# SCH_PCB_Dashboy_subboard_2023-03-29.net
KiCad netlist of a schematic drawn in EasyEDA
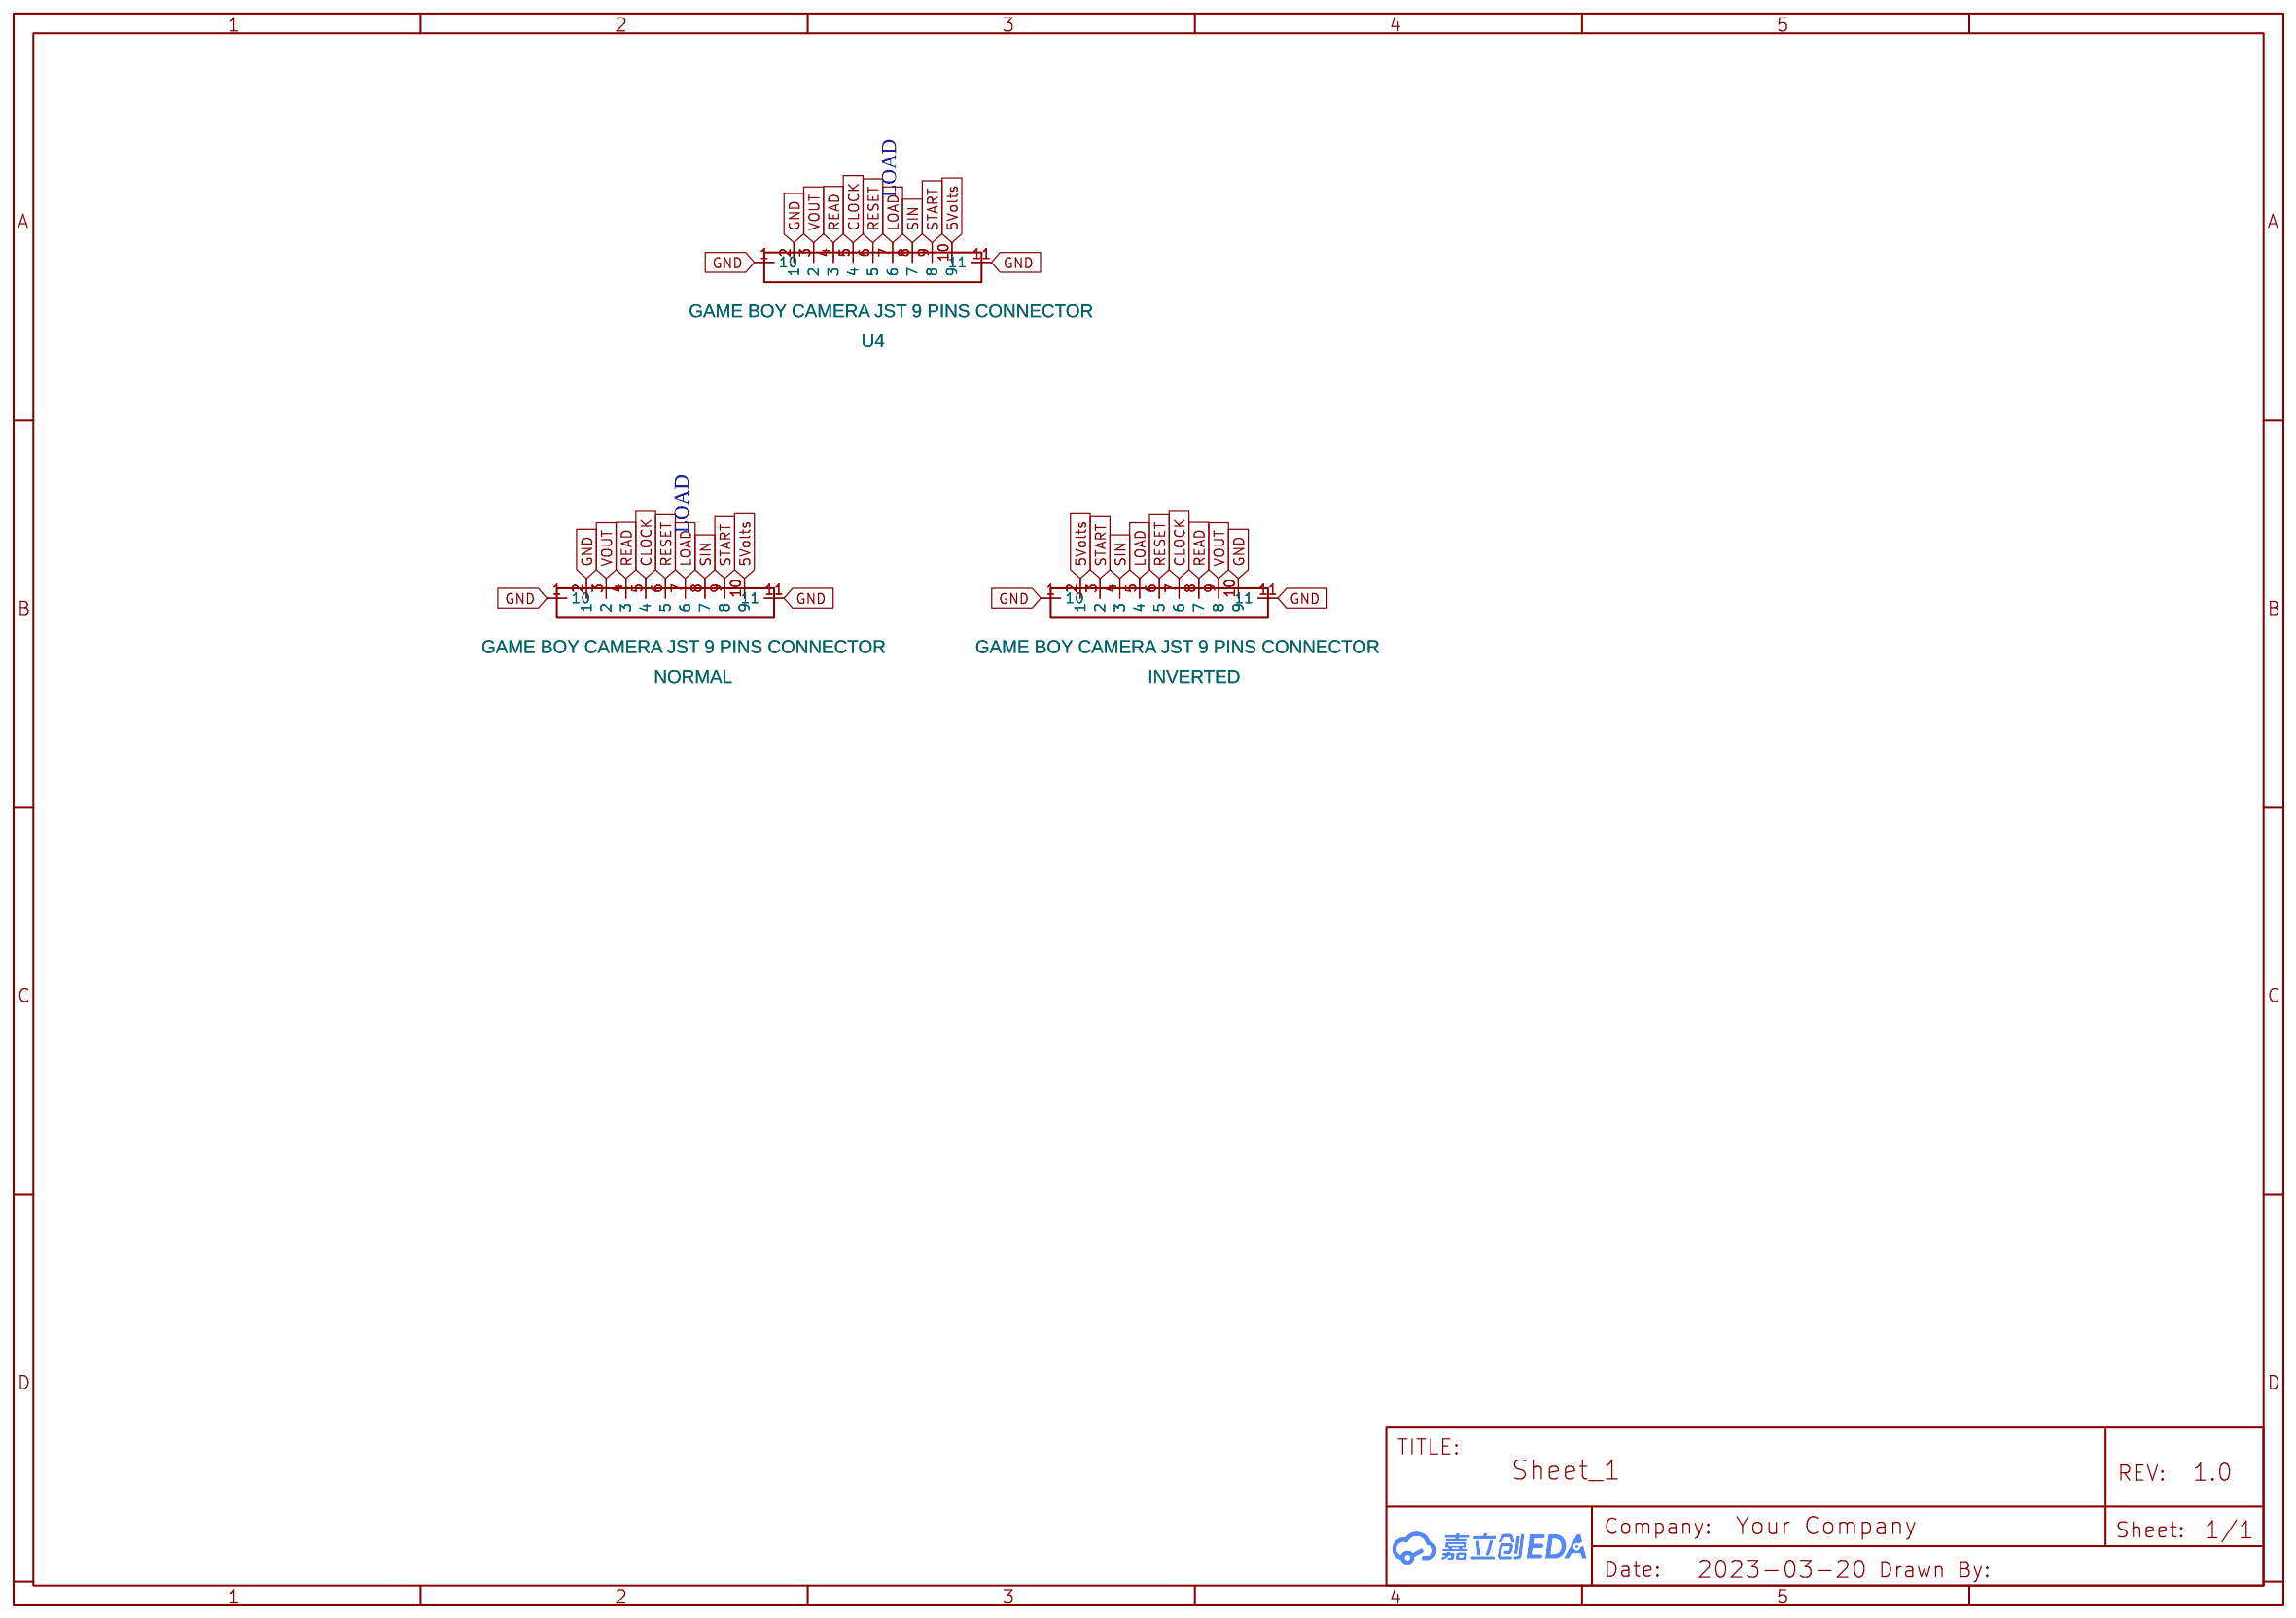
[diagram p0: schematic sheet]

(export (version "E")
  (design (tool "Eeschema 10.0.6"))
  (components
    (comp (ref "INVERTED")
      (value "GAME BOY CAMERA JST 9 PINS CONNECTOR")
      (libsource (lib "") (part "GAME BOY CAMERA JST 9 PINS CONNECTOR_2"))
    )
    (comp (ref "NORMAL")
      (value "GAME BOY CAMERA JST 9 PINS CONNECTOR")
      (libsource (lib "") (part "GAME BOY CAMERA JST 9 PINS CONNECTOR_1"))
    )
    (comp (ref "U4")
      (value "GAME BOY CAMERA JST 9 PINS CONNECTOR")
      (libsource (lib "") (part "GAME BOY CAMERA JST 9 PINS CONNECTOR"))
    )
  )
  (nets
    (net (code "1") (name "5Volts") (class "Default")
      (node (ref "INVERTED") (pin "2") (pinfunction "1_2") (pintype "unspecified"))
      (node (ref "NORMAL") (pin "10") (pinfunction "9_10") (pintype "unspecified"))
      (node (ref "U4") (pin "10") (pinfunction "9_10") (pintype "unspecified"))
    )
    (net (code "2") (name "CLOCK") (class "Default")
      (node (ref "INVERTED") (pin "7") (pinfunction "6_7") (pintype "unspecified"))
      (node (ref "NORMAL") (pin "5") (pinfunction "4_5") (pintype "unspecified"))
      (node (ref "U4") (pin "5") (pinfunction "4_5") (pintype "unspecified"))
    )
    (net (code "3") (name "GND") (class "Default")
      (node (ref "INVERTED") (pin "1") (pinfunction "10_1") (pintype "unspecified"))
      (node (ref "INVERTED") (pin "10") (pinfunction "9_10") (pintype "unspecified"))
      (node (ref "INVERTED") (pin "11") (pinfunction "11_11") (pintype "unspecified"))
      (node (ref "NORMAL") (pin "1") (pinfunction "10_1") (pintype "unspecified"))
      (node (ref "NORMAL") (pin "11") (pinfunction "11_11") (pintype "unspecified"))
      (node (ref "NORMAL") (pin "2") (pinfunction "1_2") (pintype "unspecified"))
      (node (ref "U4") (pin "1") (pinfunction "10_1") (pintype "unspecified"))
      (node (ref "U4") (pin "11") (pinfunction "11_11") (pintype "unspecified"))
      (node (ref "U4") (pin "2") (pinfunction "1_2") (pintype "unspecified"))
    )
    (net (code "4") (name "LOAD") (class "Default")
      (node (ref "INVERTED") (pin "5") (pinfunction "4_5") (pintype "unspecified"))
      (node (ref "NORMAL") (pin "7") (pinfunction "6_7") (pintype "unspecified"))
      (node (ref "U4") (pin "7") (pinfunction "6_7") (pintype "unspecified"))
    )
    (net (code "5") (name "READ") (class "Default")
      (node (ref "INVERTED") (pin "8") (pinfunction "7_8") (pintype "unspecified"))
      (node (ref "NORMAL") (pin "4") (pinfunction "3_4") (pintype "unspecified"))
      (node (ref "U4") (pin "4") (pinfunction "3_4") (pintype "unspecified"))
    )
    (net (code "6") (name "RESET") (class "Default")
      (node (ref "INVERTED") (pin "6") (pinfunction "5_6") (pintype "unspecified"))
      (node (ref "NORMAL") (pin "6") (pinfunction "5_6") (pintype "unspecified"))
      (node (ref "U4") (pin "6") (pinfunction "5_6") (pintype "unspecified"))
    )
    (net (code "7") (name "SIN") (class "Default")
      (node (ref "INVERTED") (pin "4") (pinfunction "3_4") (pintype "unspecified"))
      (node (ref "NORMAL") (pin "8") (pinfunction "7_8") (pintype "unspecified"))
      (node (ref "U4") (pin "8") (pinfunction "7_8") (pintype "unspecified"))
    )
    (net (code "8") (name "START") (class "Default")
      (node (ref "INVERTED") (pin "3") (pinfunction "2_3") (pintype "unspecified"))
      (node (ref "NORMAL") (pin "9") (pinfunction "8_9") (pintype "unspecified"))
      (node (ref "U4") (pin "9") (pinfunction "8_9") (pintype "unspecified"))
    )
    (net (code "9") (name "VOUT") (class "Default")
      (node (ref "INVERTED") (pin "9") (pinfunction "8_9") (pintype "unspecified"))
      (node (ref "NORMAL") (pin "3") (pinfunction "2_3") (pintype "unspecified"))
      (node (ref "U4") (pin "3") (pinfunction "2_3") (pintype "unspecified"))
    )
  )
)
